# FRAM-SOP_rev_B.net
KiCad netlist of a schematic drawn in EAGLE
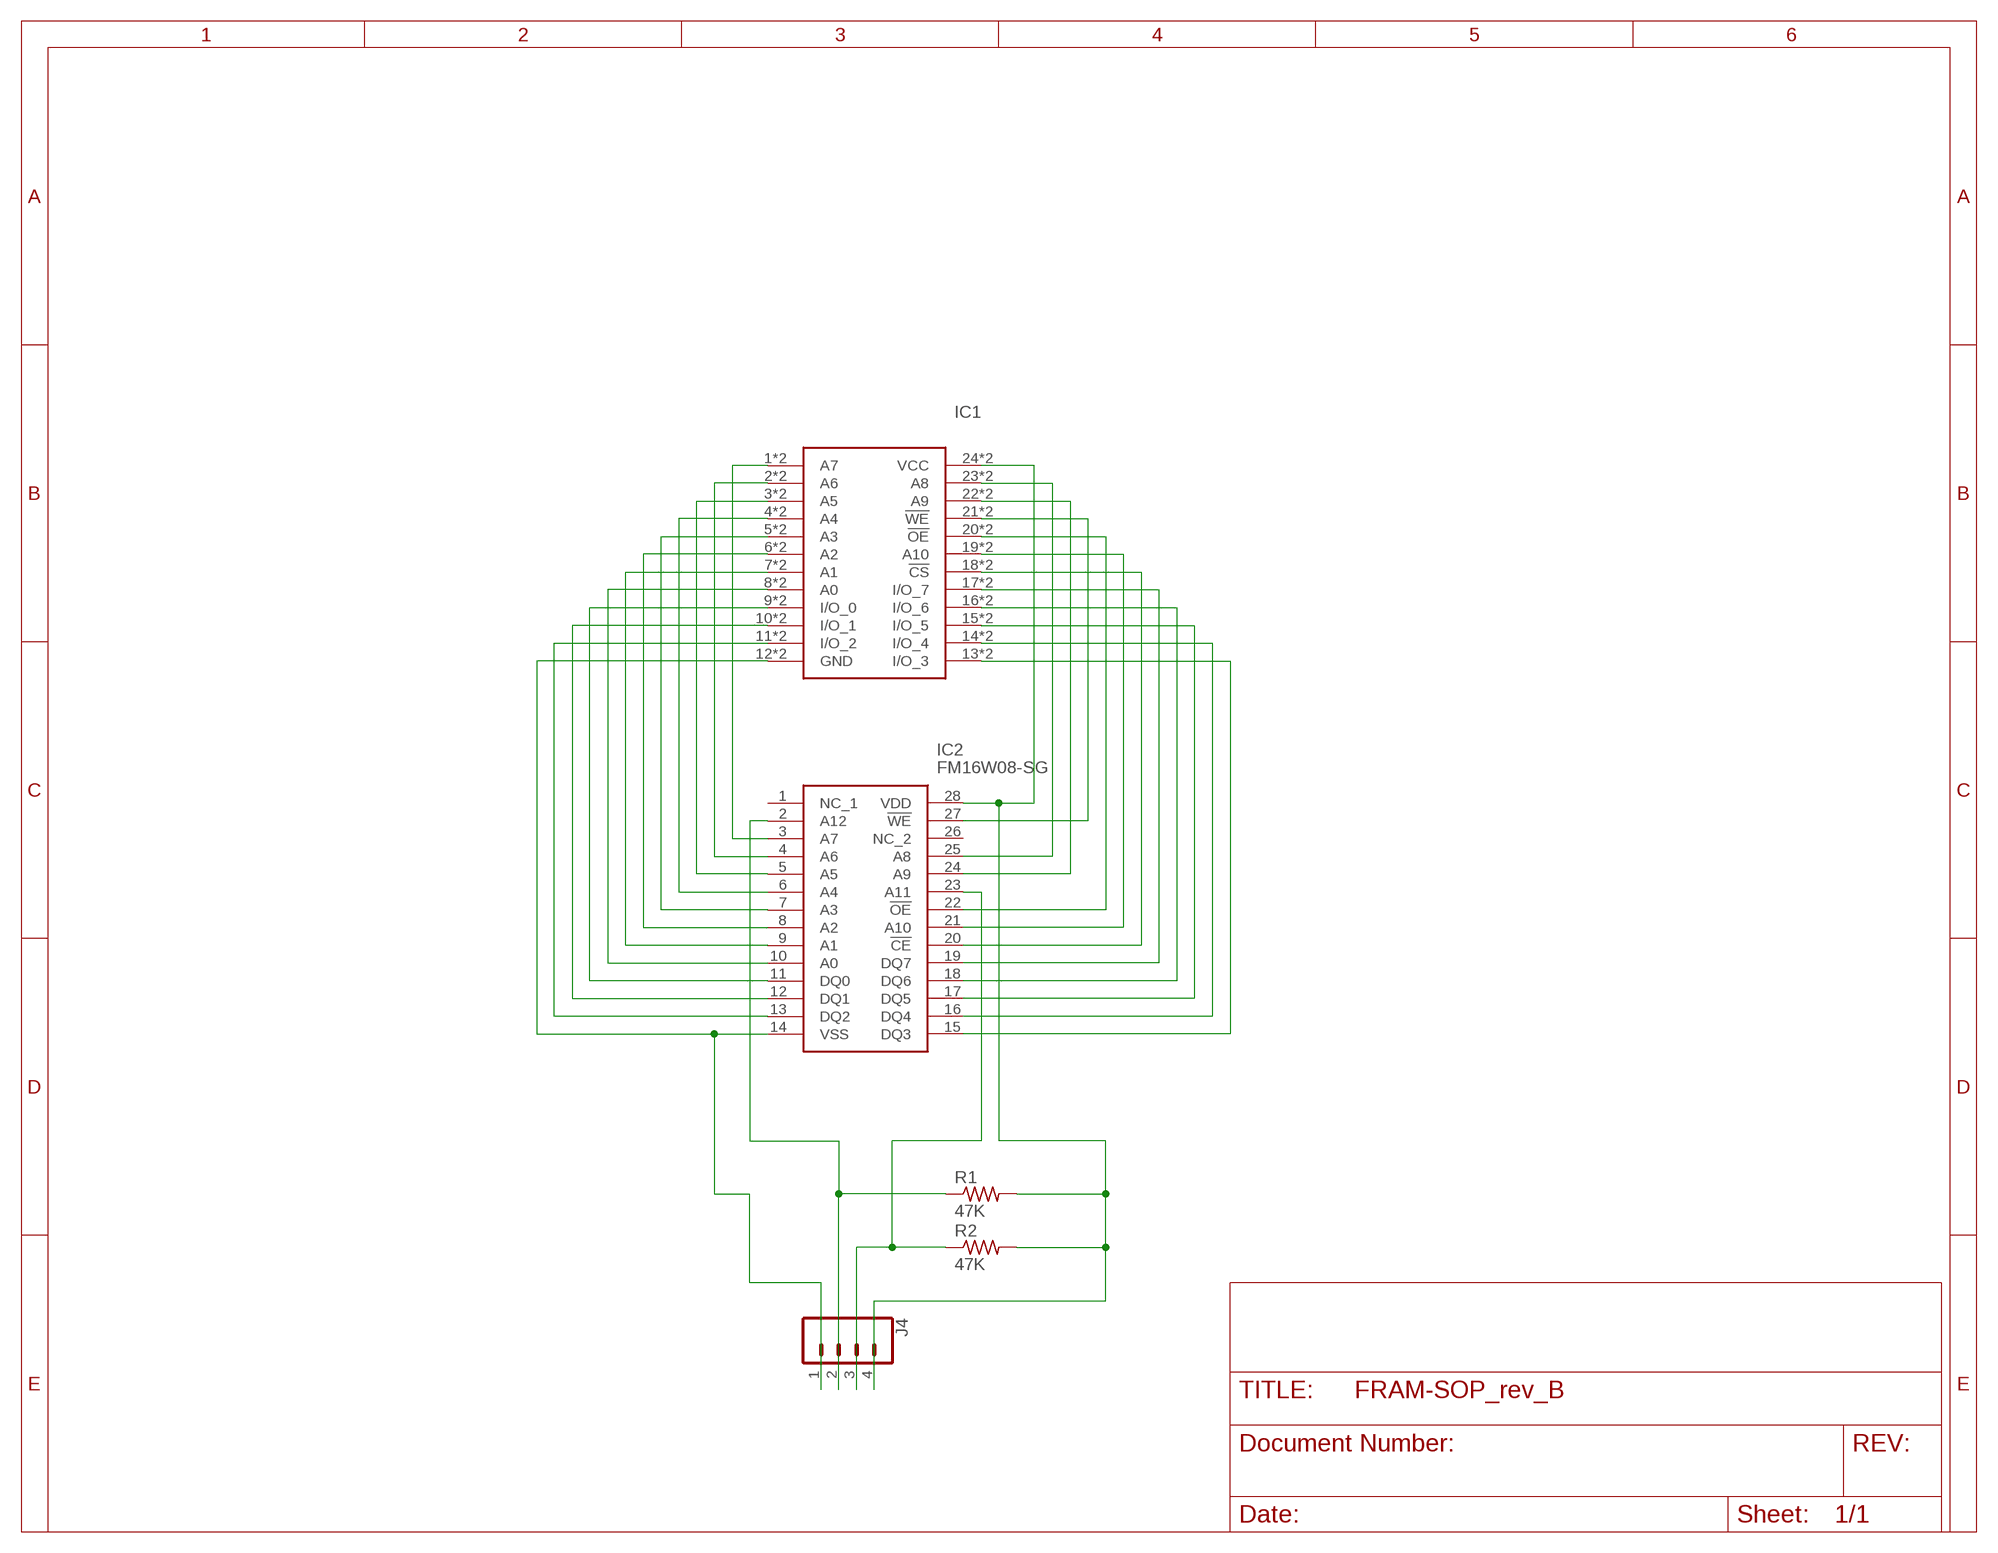
[diagram p0: schematic, sheet 1]

(export (version "E")
  (design (tool "Eeschema 10.0.6"))
  (components
    (comp (ref "IC1")
      (value "6116SOP-CASTELL")
      (footprint "eagle-import:CASTELL_SOIC-24N")
      (libsource (lib "eagle-import") (part "6116SOP-CASTELL"))
    )
    (comp (ref "IC2")
      (value "FM16W08-SG")
      (footprint "eagle-import:SOIC127P1032X267-28N")
      (fields (field (name "MOUSER_PART_NUMBER") "877-FM16W08-SG"))
      (libsource (lib "eagle-import") (part "FM16W08-SG"))
    )
    (comp (ref "J4")
      (value "CONN_04SMD_RA_FEMALE")
      (footprint "eagle-import:1X04_SMD_RA_FEMALE")
      (libsource (lib "eagle-import") (part "CONN_04SMD_RA_FEMALE"))
    )
    (comp (ref "R1")
      (value "47K")
      (footprint "eagle-import:R0603")
      (libsource (lib "eagle-import") (part "R-US_R0603"))
    )
    (comp (ref "R2")
      (value "47K")
      (footprint "eagle-import:R0603")
      (libsource (lib "eagle-import") (part "R-US_R0603"))
    )
  )
  (nets
    (net (code "1") (name "Net-(IC2-A0)") (class "Default")
      (node (ref "IC1") (pin "8") (pinfunction "A0_8") (pintype "bidirectional"))
      (node (ref "IC1") (pin "P$8") (pinfunction "A0_P$8") (pintype "bidirectional"))
      (node (ref "IC2") (pin "10") (pinfunction "A0_10") (pintype "input"))
    )
    (net (code "2") (name "Net-(IC2-A1)") (class "Default")
      (node (ref "IC1") (pin "7") (pinfunction "A1_7") (pintype "bidirectional"))
      (node (ref "IC1") (pin "P$7") (pinfunction "A1_P$7") (pintype "bidirectional"))
      (node (ref "IC2") (pin "9") (pinfunction "A1_9") (pintype "input"))
    )
    (net (code "3") (name "Net-(IC2-A2)") (class "Default")
      (node (ref "IC1") (pin "6") (pinfunction "A2_6") (pintype "bidirectional"))
      (node (ref "IC1") (pin "P$6") (pinfunction "A2_P$6") (pintype "bidirectional"))
      (node (ref "IC2") (pin "8") (pinfunction "A2_8") (pintype "input"))
    )
    (net (code "4") (name "Net-(IC2-A3)") (class "Default")
      (node (ref "IC1") (pin "5") (pinfunction "A3_5") (pintype "bidirectional"))
      (node (ref "IC1") (pin "P$5") (pinfunction "A3_P$5") (pintype "bidirectional"))
      (node (ref "IC2") (pin "7") (pinfunction "A3_7") (pintype "input"))
    )
    (net (code "5") (name "Net-(IC2-A4)") (class "Default")
      (node (ref "IC1") (pin "4") (pinfunction "A4_4") (pintype "bidirectional"))
      (node (ref "IC1") (pin "P$4") (pinfunction "A4_P$4") (pintype "bidirectional"))
      (node (ref "IC2") (pin "6") (pinfunction "A4_6") (pintype "input"))
    )
    (net (code "6") (name "Net-(IC2-A5)") (class "Default")
      (node (ref "IC1") (pin "3") (pinfunction "A5_3") (pintype "bidirectional"))
      (node (ref "IC1") (pin "P$3") (pinfunction "A5_P$3") (pintype "bidirectional"))
      (node (ref "IC2") (pin "5") (pinfunction "A5_5") (pintype "input"))
    )
    (net (code "7") (name "Net-(IC2-A6)") (class "Default")
      (node (ref "IC1") (pin "2") (pinfunction "A6_2") (pintype "bidirectional"))
      (node (ref "IC1") (pin "P$2") (pinfunction "A6_P$2") (pintype "bidirectional"))
      (node (ref "IC2") (pin "4") (pinfunction "A6_4") (pintype "input"))
    )
    (net (code "8") (name "Net-(IC2-A7)") (class "Default")
      (node (ref "IC1") (pin "1") (pinfunction "A7_1") (pintype "bidirectional"))
      (node (ref "IC1") (pin "P$1") (pinfunction "A7_P$1") (pintype "bidirectional"))
      (node (ref "IC2") (pin "3") (pinfunction "A7_3") (pintype "input"))
    )
    (net (code "9") (name "Net-(IC2-A8)") (class "Default")
      (node (ref "IC1") (pin "23") (pinfunction "A8_23") (pintype "bidirectional"))
      (node (ref "IC1") (pin "P$23") (pinfunction "A8_P$23") (pintype "bidirectional"))
      (node (ref "IC2") (pin "25") (pinfunction "A8_25") (pintype "input"))
    )
    (net (code "10") (name "Net-(IC2-A9)") (class "Default")
      (node (ref "IC1") (pin "22") (pinfunction "A9_22") (pintype "bidirectional"))
      (node (ref "IC1") (pin "P$22") (pinfunction "A9_P$22") (pintype "bidirectional"))
      (node (ref "IC2") (pin "24") (pinfunction "A9_24") (pintype "input"))
    )
    (net (code "11") (name "Net-(IC2-A10)") (class "Default")
      (node (ref "IC1") (pin "19") (pinfunction "A10_19") (pintype "bidirectional"))
      (node (ref "IC1") (pin "P$19") (pinfunction "A10_P$19") (pintype "bidirectional"))
      (node (ref "IC2") (pin "21") (pinfunction "A10_21") (pintype "input"))
    )
    (net (code "12") (name "Net-(IC2-A11)") (class "Default")
      (node (ref "IC2") (pin "23") (pinfunction "A11_23") (pintype "input"))
      (node (ref "J4") (pin "3") (pinfunction "3_3") (pintype "passive"))
      (node (ref "R2") (pin "1") (pinfunction "1_1") (pintype "passive"))
    )
    (net (code "13") (name "Net-(IC2-A12)") (class "Default")
      (node (ref "IC2") (pin "2") (pinfunction "A12_2") (pintype "input"))
      (node (ref "J4") (pin "2") (pinfunction "2_2") (pintype "passive"))
      (node (ref "R1") (pin "1") (pinfunction "1_1") (pintype "passive"))
    )
    (net (code "14") (name "Net-(IC2-DQ0)") (class "Default")
      (node (ref "IC1") (pin "9") (pinfunction "I/O_0_9") (pintype "bidirectional"))
      (node (ref "IC1") (pin "P$9") (pinfunction "I/O_0_P$9") (pintype "bidirectional"))
      (node (ref "IC2") (pin "11") (pinfunction "DQ0_11") (pintype "bidirectional"))
    )
    (net (code "15") (name "Net-(IC2-DQ1)") (class "Default")
      (node (ref "IC1") (pin "10") (pinfunction "I/O_1_10") (pintype "bidirectional"))
      (node (ref "IC1") (pin "P$10") (pinfunction "I/O_1_P$10") (pintype "bidirectional"))
      (node (ref "IC2") (pin "12") (pinfunction "DQ1_12") (pintype "bidirectional"))
    )
    (net (code "16") (name "Net-(IC2-DQ2)") (class "Default")
      (node (ref "IC1") (pin "11") (pinfunction "I/O_2_11") (pintype "bidirectional"))
      (node (ref "IC1") (pin "P$11") (pinfunction "I/O_2_P$11") (pintype "bidirectional"))
      (node (ref "IC2") (pin "13") (pinfunction "DQ2_13") (pintype "bidirectional"))
    )
    (net (code "17") (name "Net-(IC2-DQ3)") (class "Default")
      (node (ref "IC1") (pin "13") (pinfunction "I/O_3_13") (pintype "bidirectional"))
      (node (ref "IC1") (pin "P$13") (pinfunction "I/O_3_P$13") (pintype "bidirectional"))
      (node (ref "IC2") (pin "15") (pinfunction "DQ3_15") (pintype "bidirectional"))
    )
    (net (code "18") (name "Net-(IC2-DQ4)") (class "Default")
      (node (ref "IC1") (pin "14") (pinfunction "I/O_4_14") (pintype "bidirectional"))
      (node (ref "IC1") (pin "P$14") (pinfunction "I/O_4_P$14") (pintype "bidirectional"))
      (node (ref "IC2") (pin "16") (pinfunction "DQ4_16") (pintype "bidirectional"))
    )
    (net (code "19") (name "Net-(IC2-DQ5)") (class "Default")
      (node (ref "IC1") (pin "15") (pinfunction "I/O_5_15") (pintype "bidirectional"))
      (node (ref "IC1") (pin "P$15") (pinfunction "I/O_5_P$15") (pintype "bidirectional"))
      (node (ref "IC2") (pin "17") (pinfunction "DQ5_17") (pintype "bidirectional"))
    )
    (net (code "20") (name "Net-(IC2-DQ6)") (class "Default")
      (node (ref "IC1") (pin "16") (pinfunction "I/O_6_16") (pintype "bidirectional"))
      (node (ref "IC1") (pin "P$16") (pinfunction "I/O_6_P$16") (pintype "bidirectional"))
      (node (ref "IC2") (pin "18") (pinfunction "DQ6_18") (pintype "bidirectional"))
    )
    (net (code "21") (name "Net-(IC2-DQ7)") (class "Default")
      (node (ref "IC1") (pin "17") (pinfunction "I/O_7_17") (pintype "bidirectional"))
      (node (ref "IC1") (pin "P$17") (pinfunction "I/O_7_P$17") (pintype "bidirectional"))
      (node (ref "IC2") (pin "19") (pinfunction "DQ7_19") (pintype "bidirectional"))
    )
    (net (code "22") (name "Net-(IC2-VDD)") (class "Default")
      (node (ref "IC1") (pin "24") (pinfunction "VCC_24") (pintype "bidirectional"))
      (node (ref "IC1") (pin "P$24") (pinfunction "VCC_P$24") (pintype "bidirectional"))
      (node (ref "IC2") (pin "28") (pinfunction "VDD_28") (pintype "power_in"))
      (node (ref "J4") (pin "4") (pinfunction "4_4") (pintype "passive"))
      (node (ref "R1") (pin "2") (pinfunction "2_2") (pintype "passive"))
      (node (ref "R2") (pin "2") (pinfunction "2_2") (pintype "passive"))
    )
    (net (code "23") (name "Net-(IC2-VSS)") (class "Default")
      (node (ref "IC1") (pin "12") (pinfunction "GND_12") (pintype "bidirectional"))
      (node (ref "IC1") (pin "P$12") (pinfunction "GND_P$12") (pintype "bidirectional"))
      (node (ref "IC2") (pin "14") (pinfunction "VSS_14") (pintype "power_in"))
      (node (ref "J4") (pin "1") (pinfunction "1_1") (pintype "passive"))
    )
    (net (code "24") (name "Net-(IC2-~{CE})") (class "Default")
      (node (ref "IC1") (pin "18") (pinfunction "~{CS}_18") (pintype "bidirectional"))
      (node (ref "IC1") (pin "P$18") (pinfunction "~{CS}_P$18") (pintype "bidirectional"))
      (node (ref "IC2") (pin "20") (pinfunction "~{CE}_20") (pintype "input"))
    )
    (net (code "25") (name "Net-(IC2-~{OE})") (class "Default")
      (node (ref "IC1") (pin "20") (pinfunction "~{OE}_20") (pintype "bidirectional"))
      (node (ref "IC1") (pin "P$20") (pinfunction "~{OE}_P$20") (pintype "bidirectional"))
      (node (ref "IC2") (pin "22") (pinfunction "~{OE}_22") (pintype "input"))
    )
    (net (code "26") (name "Net-(IC2-~{WE})") (class "Default")
      (node (ref "IC1") (pin "21") (pinfunction "~{WE}_21") (pintype "bidirectional"))
      (node (ref "IC1") (pin "P$21") (pinfunction "~{WE}_P$21") (pintype "bidirectional"))
      (node (ref "IC2") (pin "27") (pinfunction "~{WE}_27") (pintype "input"))
    )
    (net (code "27") (name "unconnected-(IC2-NC_1-Pad1)") (class "Default")
      (node (ref "IC2") (pin "1") (pinfunction "NC_1_1") (pintype "bidirectional"))
    )
    (net (code "28") (name "unconnected-(IC2-NC_2-Pad26)") (class "Default")
      (node (ref "IC2") (pin "26") (pinfunction "NC_2_26") (pintype "bidirectional"))
    )
  )
)
